# LED.net
KiCad netlist of a schematic drawn in Altium Designer
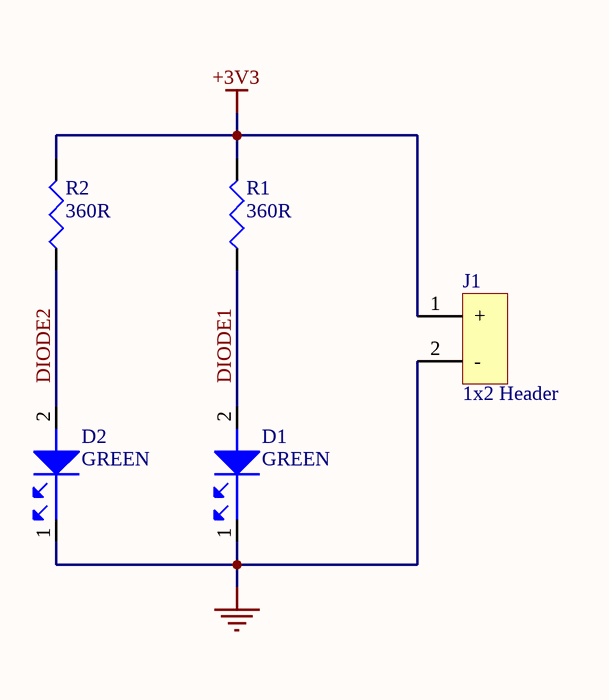
[diagram p0: LED.SchDoc]

(export (version "E")
  (design (tool "Eeschema 10.0.6"))
  (components
    (comp (ref "D1")
      (value "GREEN")
      (footprint "LED0603G")
      (description "LED SM 0603 3V -/1000/-MCD GREEN")
      (fields
        (field (name "MANUFACTURER") "Visual Communications")
        (field (name "MANUFACTURER PART NUMBER") "LSM0603453V")
      )
      (libsource (lib "LED_Schlib") (part "LSM0603453V"))
    )
    (comp (ref "D2")
      (value "GREEN")
      (footprint "LED0603G")
      (description "LED SM 0603 3V -/1000/-MCD GREEN")
      (fields
        (field (name "MANUFACTURER") "Visual Communications")
        (field (name "MANUFACTURER PART NUMBER") "LSM0603453V")
      )
      (libsource (lib "LED_Schlib") (part "LSM0603453V"))
    )
    (comp (ref "J1")
      (value "1x2 Header")
      (footprint "HDR1x2")
      (description "CONN HEADER VERT 2POS 2.54MM")
      (fields (field (name "MANUFACTURER") "Molex") (field (name "MANUFACTURER PART NUMBER") "22-27-2021"))
      (libsource (lib "LED_Schlib") (part "22-27-2021"))
    )
    (comp (ref "R1")
      (value "360R")
      (footprint "R0805")
      (description "RES SMD 360 OHM 1% 1/8W 0805")
      (fields
        (field (name "MANUFACTURER") "Yageo")
        (field (name "MANUFACTURER PART NUMBER") "AC0805FR-07360RL")
      )
      (libsource (lib "LED_Schlib") (part "AC0805FR-07360RL"))
    )
    (comp (ref "R2")
      (value "360R")
      (footprint "R0805")
      (description "RES SMD 360 OHM 1% 1/8W 0805")
      (fields
        (field (name "MANUFACTURER") "Yageo")
        (field (name "MANUFACTURER PART NUMBER") "AC0805FR-07360RL")
      )
      (libsource (lib "LED_Schlib") (part "AC0805FR-07360RL"))
    )
  )
  (nets
    (net (code "1") (name "+3V3") (class "Default")
      (node (ref "J1") (pin "1") (pinfunction "+_1") (pintype "passive"))
      (node (ref "R1") (pin "2") (pinfunction "2_2") (pintype "passive"))
      (node (ref "R2") (pin "2") (pinfunction "2_2") (pintype "passive"))
    )
    (net (code "2") (name "/DIODE1") (class "Default")
      (node (ref "D1") (pin "2") (pinfunction "2_2") (pintype "passive"))
      (node (ref "R1") (pin "1") (pinfunction "1_1") (pintype "passive"))
    )
    (net (code "3") (name "/DIODE2") (class "Default")
      (node (ref "D2") (pin "2") (pinfunction "2_2") (pintype "passive"))
      (node (ref "R2") (pin "1") (pinfunction "1_1") (pintype "passive"))
    )
    (net (code "4") (name "GND") (class "Default")
      (node (ref "D1") (pin "1") (pinfunction "1_1") (pintype "passive"))
      (node (ref "D2") (pin "1") (pinfunction "1_1") (pintype "passive"))
      (node (ref "J1") (pin "2") (pinfunction "-_2") (pintype "passive"))
    )
  )
)
